# IARC_GR_Shield.net
KiCad netlist of a schematic drawn in EAGLE
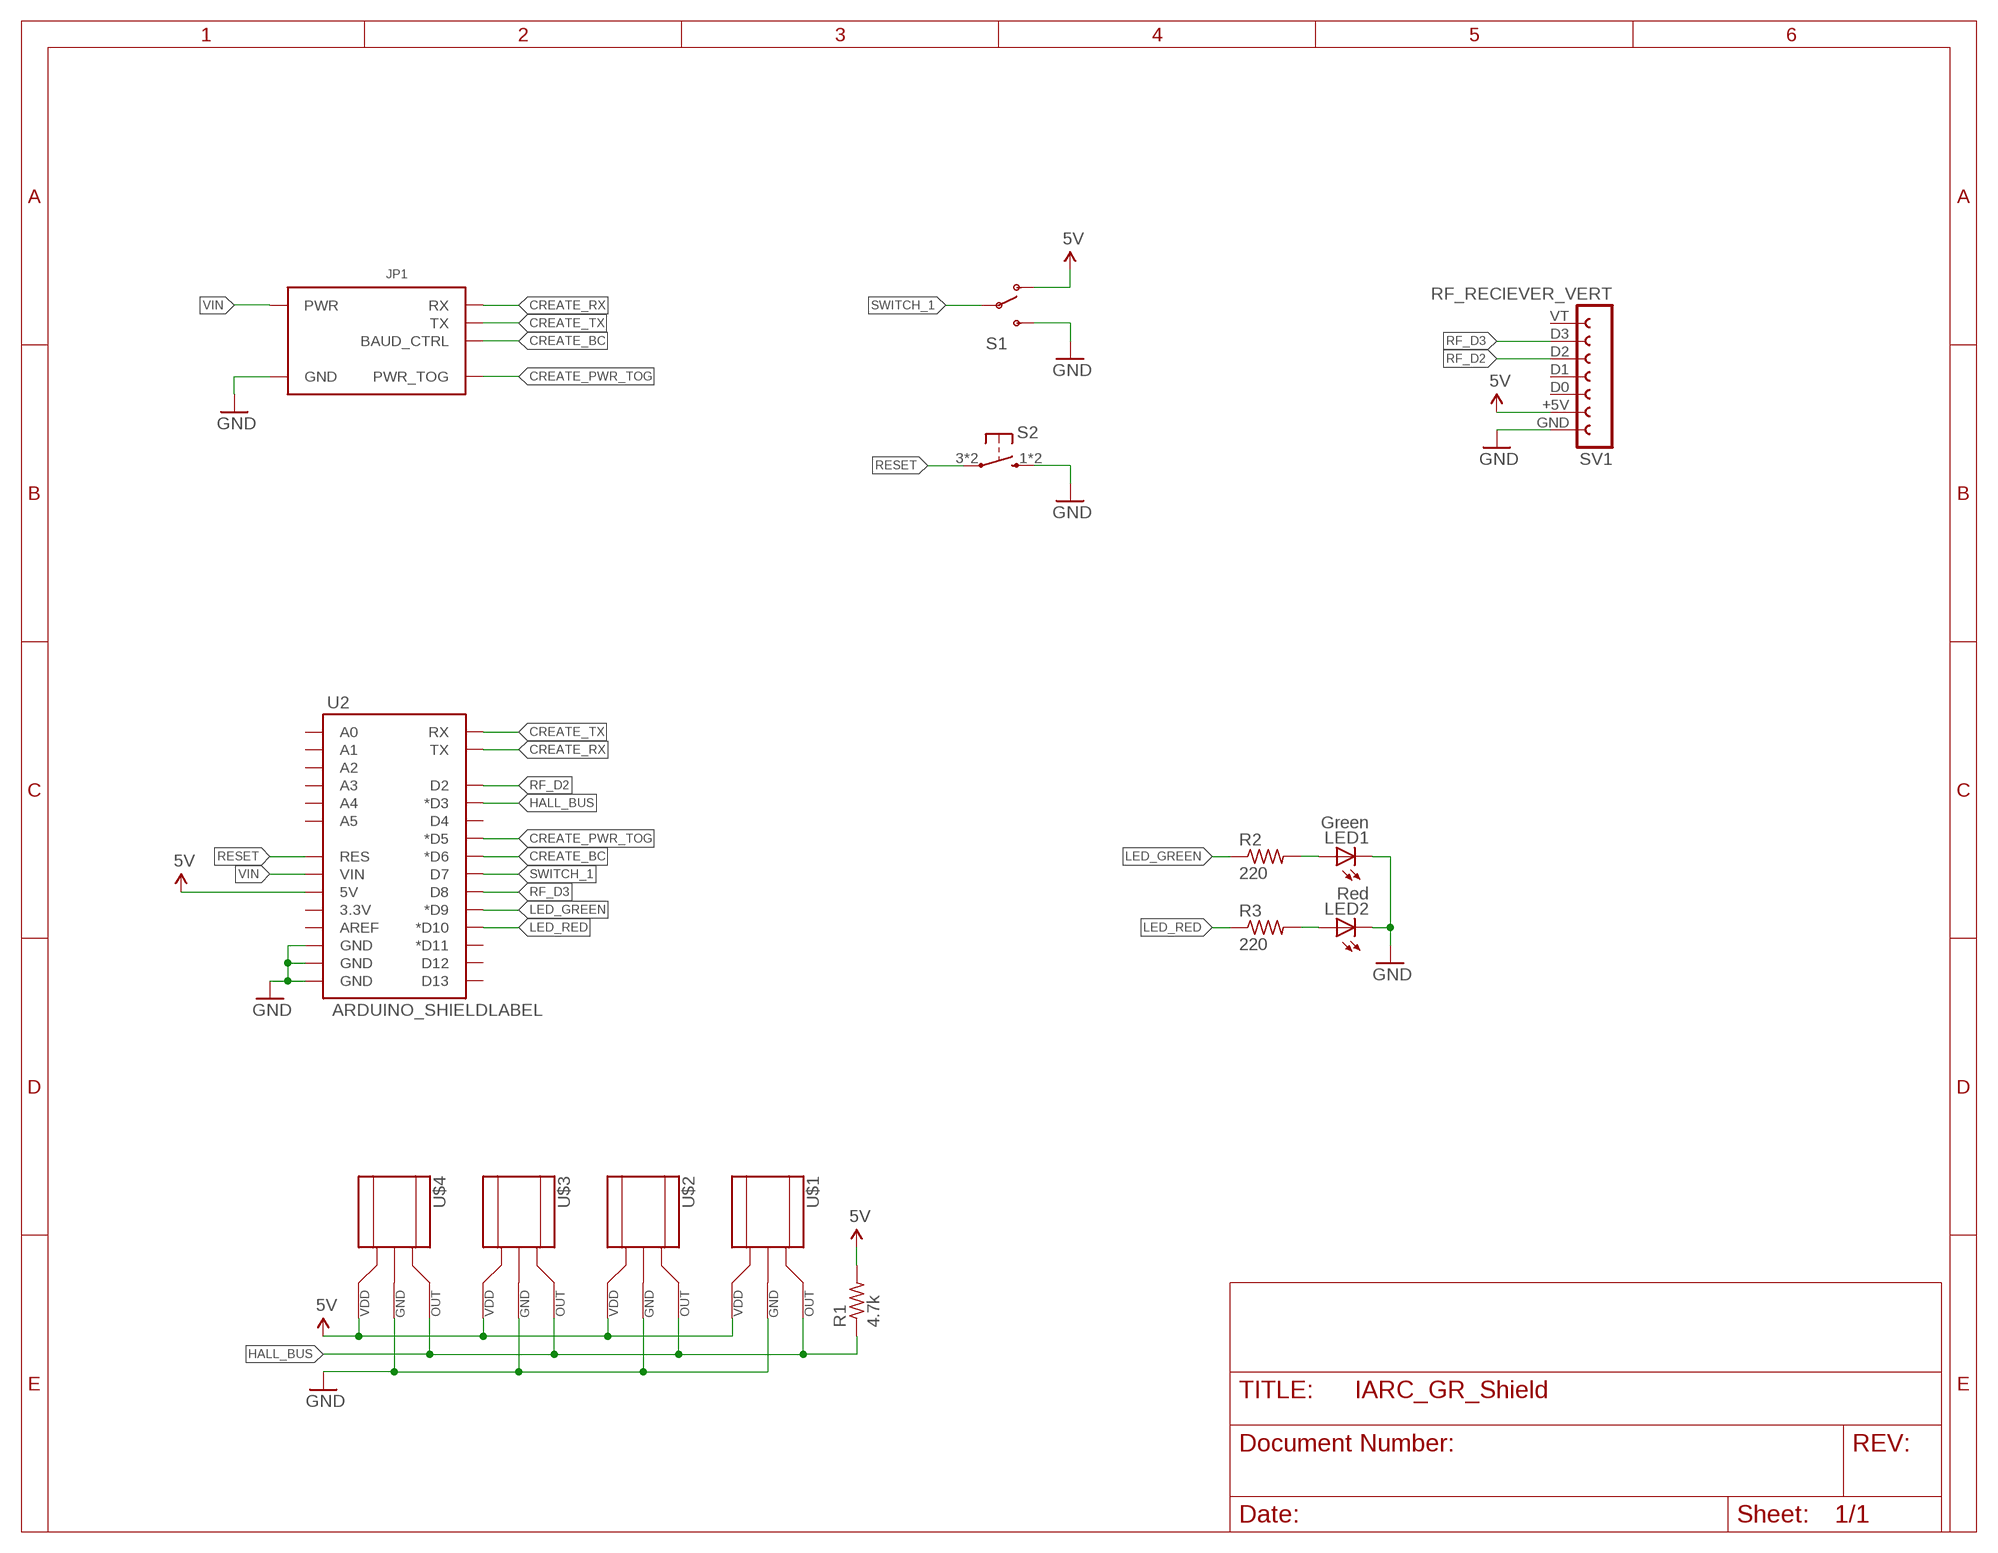
[diagram p0: schematic, sheet 1]

(export (version "E")
  (design (tool "Eeschema 10.0.6"))
  (components
    (comp (ref "JP1")
      (value "IROBOT_CREATE_IARC_HOOKUP")
      (footprint "eagle-import:2X5-SHROUDED")
      (libsource (lib "eagle-import") (part "IROBOT_CREATE_IARC_HOOKUP"))
    )
    (comp (ref "LED1")
      (value "Green")
      (footprint "eagle-import:LED5MM")
      (libsource (lib "eagle-import") (part "LED5MM"))
    )
    (comp (ref "LED2")
      (value "Red")
      (footprint "eagle-import:LED5MM")
      (libsource (lib "eagle-import") (part "LED5MM"))
    )
    (comp (ref "R1")
      (value "4.7k")
      (footprint "eagle-import:0207_10")
      (libsource (lib "eagle-import") (part "R-US_0207/10"))
    )
    (comp (ref "R2")
      (value "220")
      (footprint "eagle-import:0207_10")
      (libsource (lib "eagle-import") (part "R-US_0207/10"))
    )
    (comp (ref "R3")
      (value "220")
      (footprint "eagle-import:0207_10")
      (libsource (lib "eagle-import") (part "R-US_0207/10"))
    )
    (comp (ref "S1")
      (value "SWITCH-SPDTTHRU-VERT")
      (footprint "eagle-import:SWITCH-SPDT_THRU-VERT")
      (libsource (lib "eagle-import") (part "SWITCH-SPDTTHRU-VERT"))
    )
    (comp (ref "S2")
      (value "TACT_BUTTON_THRU-HOLE")
      (footprint "eagle-import:SIMPLE_BUTTON")
      (fields (field (name "MPN") "B3F-1000"))
      (libsource (lib "eagle-import") (part "TACT_BUTTON_THRU-HOLE"))
    )
    (comp (ref "SV1")
      (value "RF_RECIEVER_VERT")
      (footprint "eagle-import:RF_RECIEVER_VERT")
      (fields (field (name "MF") "Sulins") (field (name "MPN") "PPTC071LFBN-RC"))
      (libsource (lib "eagle-import") (part "RF_RECIEVER_VERT"))
    )
    (comp (ref "U$1")
      (value "HALL_EFFECTHEADER")
      (footprint "eagle-import:1X03")
      (libsource (lib "eagle-import") (part "HALL_EFFECTHEADER"))
    )
    (comp (ref "U$2")
      (value "HALL_EFFECTHEADER")
      (footprint "eagle-import:1X03")
      (libsource (lib "eagle-import") (part "HALL_EFFECTHEADER"))
    )
    (comp (ref "U$3")
      (value "HALL_EFFECTHEADER")
      (footprint "eagle-import:1X03")
      (libsource (lib "eagle-import") (part "HALL_EFFECTHEADER"))
    )
    (comp (ref "U$4")
      (value "HALL_EFFECTHEADER")
      (footprint "eagle-import:1X03")
      (libsource (lib "eagle-import") (part "HALL_EFFECTHEADER"))
    )
    (comp (ref "U2")
      (value "ARDUINO_SHIELDLABEL")
      (footprint "eagle-import:DUEMILANOVE_SHIELD")
      (libsource (lib "eagle-import") (part "ARDUINO_SHIELDLABEL"))
    )
  )
  (nets
    (net (code "1") (name "5V") (class "Default")
      (node (ref "R1") (pin "2") (pinfunction "2_2") (pintype "passive"))
      (node (ref "S1") (pin "1") (pinfunction "O_1") (pintype "passive"))
      (node (ref "SV1") (pin "+5V") (pinfunction "+5V_+5V") (pintype "power_in"))
      (node (ref "U$1") (pin "1") (pinfunction "VDD_1") (pintype "power_in"))
      (node (ref "U$2") (pin "1") (pinfunction "VDD_1") (pintype "power_in"))
      (node (ref "U$3") (pin "1") (pinfunction "VDD_1") (pintype "power_in"))
      (node (ref "U$4") (pin "1") (pinfunction "VDD_1") (pintype "power_in"))
      (node (ref "U2") (pin "5V") (pinfunction "5V_5V") (pintype "bidirectional"))
    )
    (net (code "2") (name "CREATE_BC") (class "Default")
      (node (ref "JP1") (pin "3") (pinfunction "BAUD_CTRL_3") (pintype "bidirectional"))
      (node (ref "U2") (pin "D6") (pinfunction "*D6_D6") (pintype "bidirectional"))
    )
    (net (code "3") (name "CREATE_PWR_TOG") (class "Default")
      (node (ref "JP1") (pin "5") (pinfunction "PWR_TOG_5") (pintype "bidirectional"))
      (node (ref "U2") (pin "D5") (pinfunction "*D5_D5") (pintype "bidirectional"))
    )
    (net (code "4") (name "CREATE_RX") (class "Default")
      (node (ref "JP1") (pin "4") (pinfunction "RX_4") (pintype "bidirectional"))
      (node (ref "U2") (pin "TX") (pinfunction "TX_TX") (pintype "bidirectional"))
    )
    (net (code "5") (name "CREATE_TX") (class "Default")
      (node (ref "JP1") (pin "1") (pinfunction "TX_1") (pintype "bidirectional"))
      (node (ref "U2") (pin "RX") (pinfunction "RX_RX") (pintype "bidirectional"))
    )
    (net (code "6") (name "GND") (class "Default")
      (node (ref "JP1") (pin "2") (pinfunction "GND_2") (pintype "power_in"))
      (node (ref "LED1") (pin "K") (pinfunction "C_K") (pintype "passive"))
      (node (ref "LED2") (pin "K") (pinfunction "C_K") (pintype "passive"))
      (node (ref "S1") (pin "3") (pinfunction "S_3") (pintype "passive"))
      (node (ref "S2") (pin "1") (pinfunction "S_1") (pintype "passive"))
      (node (ref "S2") (pin "2") (pinfunction "S_2") (pintype "passive"))
      (node (ref "SV1") (pin "GND") (pinfunction "GND_GND") (pintype "power_in"))
      (node (ref "U$1") (pin "2") (pinfunction "GND_2") (pintype "power_in"))
      (node (ref "U$2") (pin "2") (pinfunction "GND_2") (pintype "power_in"))
      (node (ref "U$3") (pin "2") (pinfunction "GND_2") (pintype "power_in"))
      (node (ref "U$4") (pin "2") (pinfunction "GND_2") (pintype "power_in"))
      (node (ref "U2") (pin "GND@0") (pinfunction "GND_GND@0") (pintype "bidirectional"))
      (node (ref "U2") (pin "GND@1") (pinfunction "GND_GND@1") (pintype "bidirectional"))
      (node (ref "U2") (pin "GND@2") (pinfunction "GND_GND@2") (pintype "bidirectional"))
    )
    (net (code "7") (name "HALL_BUS") (class "Default")
      (node (ref "R1") (pin "1") (pinfunction "1_1") (pintype "passive"))
      (node (ref "U$1") (pin "3") (pinfunction "OUT_3") (pintype "passive"))
      (node (ref "U$2") (pin "3") (pinfunction "OUT_3") (pintype "passive"))
      (node (ref "U$3") (pin "3") (pinfunction "OUT_3") (pintype "passive"))
      (node (ref "U$4") (pin "3") (pinfunction "OUT_3") (pintype "passive"))
      (node (ref "U2") (pin "D3") (pinfunction "*D3_D3") (pintype "bidirectional"))
    )
    (net (code "8") (name "LED_GREEN") (class "Default")
      (node (ref "R2") (pin "1") (pinfunction "1_1") (pintype "passive"))
      (node (ref "U2") (pin "D9") (pinfunction "*D9_D9") (pintype "bidirectional"))
    )
    (net (code "9") (name "LED_RED") (class "Default")
      (node (ref "R3") (pin "1") (pinfunction "1_1") (pintype "passive"))
      (node (ref "U2") (pin "D10") (pinfunction "*D10_D10") (pintype "bidirectional"))
    )
    (net (code "10") (name "Net-(LED1-PadA)") (class "Default")
      (node (ref "LED1") (pin "A") (pinfunction "A_A") (pintype "passive"))
      (node (ref "R2") (pin "2") (pinfunction "2_2") (pintype "passive"))
    )
    (net (code "11") (name "Net-(LED2-PadA)") (class "Default")
      (node (ref "LED2") (pin "A") (pinfunction "A_A") (pintype "passive"))
      (node (ref "R3") (pin "2") (pinfunction "2_2") (pintype "passive"))
    )
    (net (code "12") (name "RESET") (class "Default")
      (node (ref "S2") (pin "3") (pinfunction "P_3") (pintype "passive"))
      (node (ref "S2") (pin "4") (pinfunction "P_4") (pintype "passive"))
      (node (ref "U2") (pin "RES") (pinfunction "RES_RES") (pintype "bidirectional"))
    )
    (net (code "13") (name "RF_D2") (class "Default")
      (node (ref "SV1") (pin "D2") (pinfunction "D2_D2") (pintype "bidirectional"))
      (node (ref "U2") (pin "D2") (pinfunction "D2_D2") (pintype "bidirectional"))
    )
    (net (code "14") (name "RF_D3") (class "Default")
      (node (ref "SV1") (pin "D3") (pinfunction "D3_D3") (pintype "bidirectional"))
      (node (ref "U2") (pin "D8") (pinfunction "D8_D8") (pintype "bidirectional"))
    )
    (net (code "15") (name "SWITCH_1") (class "Default")
      (node (ref "S1") (pin "2") (pinfunction "P_2") (pintype "passive"))
      (node (ref "U2") (pin "D7") (pinfunction "D7_D7") (pintype "bidirectional"))
    )
    (net (code "16") (name "VIN") (class "Default")
      (node (ref "JP1") (pin "6") (pinfunction "PWR_6") (pintype "power_in"))
      (node (ref "U2") (pin "VIN") (pinfunction "VIN_VIN") (pintype "bidirectional"))
    )
    (net (code "17") (name "unconnected-(SV1-PadD0)") (class "Default")
      (node (ref "SV1") (pin "D0") (pinfunction "D0_D0") (pintype "bidirectional"))
    )
    (net (code "18") (name "unconnected-(SV1-PadD1)") (class "Default")
      (node (ref "SV1") (pin "D1") (pinfunction "D1_D1") (pintype "bidirectional"))
    )
    (net (code "19") (name "unconnected-(SV1-PadVT)") (class "Default")
      (node (ref "SV1") (pin "VT") (pinfunction "VT_VT") (pintype "passive"))
    )
    (net (code "20") (name "unconnected-(U2-*D11-PadD11)") (class "Default")
      (node (ref "U2") (pin "D11") (pinfunction "*D11_D11") (pintype "bidirectional"))
    )
    (net (code "21") (name "unconnected-(U2-Pad3.3V)") (class "Default")
      (node (ref "U2") (pin "3.3V") (pinfunction "3.3V_3.3V") (pintype "bidirectional"))
    )
    (net (code "22") (name "unconnected-(U2-PadA0)") (class "Default")
      (node (ref "U2") (pin "A0") (pinfunction "A0_A0") (pintype "bidirectional"))
    )
    (net (code "23") (name "unconnected-(U2-PadA1)") (class "Default")
      (node (ref "U2") (pin "A1") (pinfunction "A1_A1") (pintype "bidirectional"))
    )
    (net (code "24") (name "unconnected-(U2-PadA2)") (class "Default")
      (node (ref "U2") (pin "A2") (pinfunction "A2_A2") (pintype "bidirectional"))
    )
    (net (code "25") (name "unconnected-(U2-PadA3)") (class "Default")
      (node (ref "U2") (pin "A3") (pinfunction "A3_A3") (pintype "bidirectional"))
    )
    (net (code "26") (name "unconnected-(U2-PadA4)") (class "Default")
      (node (ref "U2") (pin "A4") (pinfunction "A4_A4") (pintype "bidirectional"))
    )
    (net (code "27") (name "unconnected-(U2-PadA5)") (class "Default")
      (node (ref "U2") (pin "A5") (pinfunction "A5_A5") (pintype "bidirectional"))
    )
    (net (code "28") (name "unconnected-(U2-PadAREF)") (class "Default")
      (node (ref "U2") (pin "AREF") (pinfunction "AREF_AREF") (pintype "bidirectional"))
    )
    (net (code "29") (name "unconnected-(U2-PadD4)") (class "Default")
      (node (ref "U2") (pin "D4") (pinfunction "D4_D4") (pintype "bidirectional"))
    )
    (net (code "30") (name "unconnected-(U2-PadD12)") (class "Default")
      (node (ref "U2") (pin "D12") (pinfunction "D12_D12") (pintype "bidirectional"))
    )
    (net (code "31") (name "unconnected-(U2-PadD13)") (class "Default")
      (node (ref "U2") (pin "D13") (pinfunction "D13_D13") (pintype "bidirectional"))
    )
  )
)
